# lampeggio_led.net
KiCad netlist of a schematic drawn in EAGLE
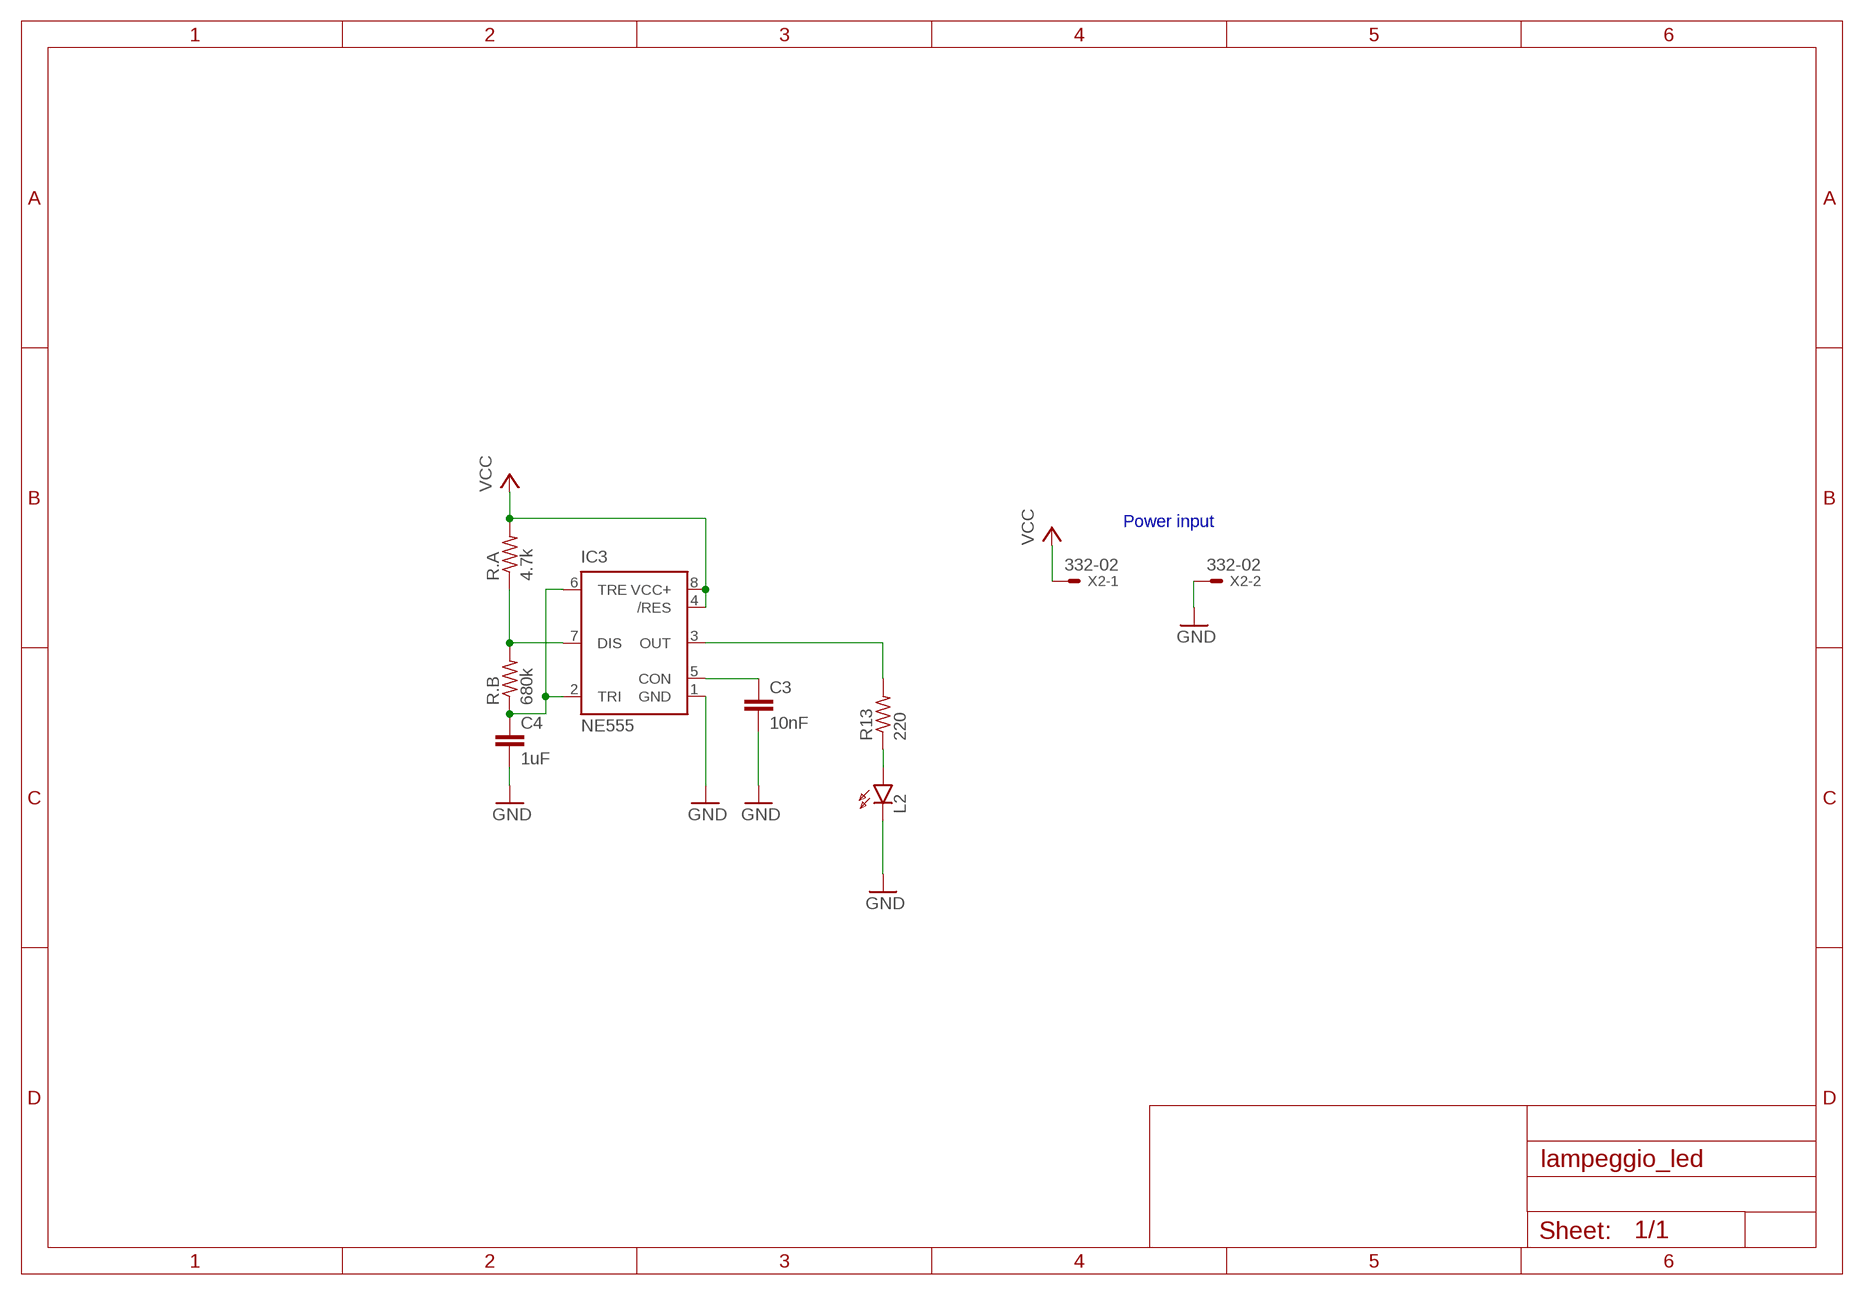
[diagram p0: schematic, sheet 1]

(export (version "E")
  (design (tool "Eeschema 10.0.6"))
  (components
    (comp (ref "C3")
      (value "10nF")
      (footprint "eagle-import:C025-024X044")
      (libsource (lib "eagle-import") (part "C-EU025-024X044"))
    )
    (comp (ref "C4")
      (value "1uF")
      (footprint "eagle-import:C025-024X044")
      (libsource (lib "eagle-import") (part "C-EU025-024X044"))
    )
    (comp (ref "IC3")
      (value "NE555")
      (footprint "eagle-import:DIL-08")
      (fields (field (name "MF") "Arrow Electronics") (field (name "MPN") "NE555N"))
      (libsource (lib "eagle-import") (part "NE555"))
    )
    (comp (ref "L2")
      (value "HLMP6")
      (footprint "eagle-import:HLMP6")
      (fields (field (name "MF") "AGILENT TECHNOLOGIES") (field (name "MPN") "HLMP-6500"))
      (libsource (lib "eagle-import") (part "HLMP6"))
    )
    (comp (ref "R.A")
      (value "4.7k")
      (footprint "eagle-import:0207_10")
      (libsource (lib "eagle-import") (part "R-US_0207/10"))
    )
    (comp (ref "R.B")
      (value "680k")
      (footprint "eagle-import:0207_10")
      (libsource (lib "eagle-import") (part "R-US_0207/10"))
    )
    (comp (ref "R13")
      (value "220")
      (footprint "eagle-import:0207_10")
      (libsource (lib "eagle-import") (part "R-US_0207/10"))
    )
    (comp (ref "X2")
      (value "332-02")
      (footprint "eagle-import:332-02")
      (libsource (lib "eagle-import") (part "332-02"))
    )
  )
  (nets
    (net (code "1") (name "GND") (class "Default")
      (node (ref "C3") (pin "2") (pinfunction "2_2") (pintype "passive"))
      (node (ref "C4") (pin "2") (pinfunction "2_2") (pintype "passive"))
      (node (ref "IC3") (pin "1") (pinfunction "GND_1") (pintype "power_in"))
      (node (ref "L2") (pin "K") (pinfunction "K_K") (pintype "passive"))
      (node (ref "X2") (pin "2") (pinfunction "S_2") (pintype "passive"))
    )
    (net (code "2") (name "Net-(IC3-CON)") (class "Default")
      (node (ref "C3") (pin "1") (pinfunction "1_1") (pintype "passive"))
      (node (ref "IC3") (pin "5") (pinfunction "CON_5") (pintype "input"))
    )
    (net (code "3") (name "Net-(IC3-DIS)") (class "Default")
      (node (ref "IC3") (pin "7") (pinfunction "DIS_7") (pintype "input"))
      (node (ref "R.A") (pin "1") (pinfunction "1_1") (pintype "passive"))
      (node (ref "R.B") (pin "2") (pinfunction "2_2") (pintype "passive"))
    )
    (net (code "4") (name "Net-(IC3-OUT)") (class "Default")
      (node (ref "IC3") (pin "3") (pinfunction "OUT_3") (pintype "output"))
      (node (ref "R13") (pin "2") (pinfunction "2_2") (pintype "passive"))
    )
    (net (code "5") (name "Net-(IC3-TRE)") (class "Default")
      (node (ref "C4") (pin "1") (pinfunction "1_1") (pintype "passive"))
      (node (ref "IC3") (pin "2") (pinfunction "TRI_2") (pintype "input"))
      (node (ref "IC3") (pin "6") (pinfunction "TRE_6") (pintype "input"))
      (node (ref "R.B") (pin "1") (pinfunction "1_1") (pintype "passive"))
    )
    (net (code "6") (name "Net-(L2-PadA)") (class "Default")
      (node (ref "L2") (pin "A") (pinfunction "A_A") (pintype "passive"))
      (node (ref "R13") (pin "1") (pinfunction "1_1") (pintype "passive"))
    )
    (net (code "7") (name "VCC") (class "Default")
      (node (ref "IC3") (pin "4") (pinfunction "/RES_4") (pintype "input"))
      (node (ref "IC3") (pin "8") (pinfunction "VCC+_8") (pintype "power_in"))
      (node (ref "R.A") (pin "2") (pinfunction "2_2") (pintype "passive"))
      (node (ref "X2") (pin "1") (pinfunction "S_1") (pintype "passive"))
    )
  )
)
